# V2d_PCB.net
KiCad netlist of a schematic drawn in EAGLE
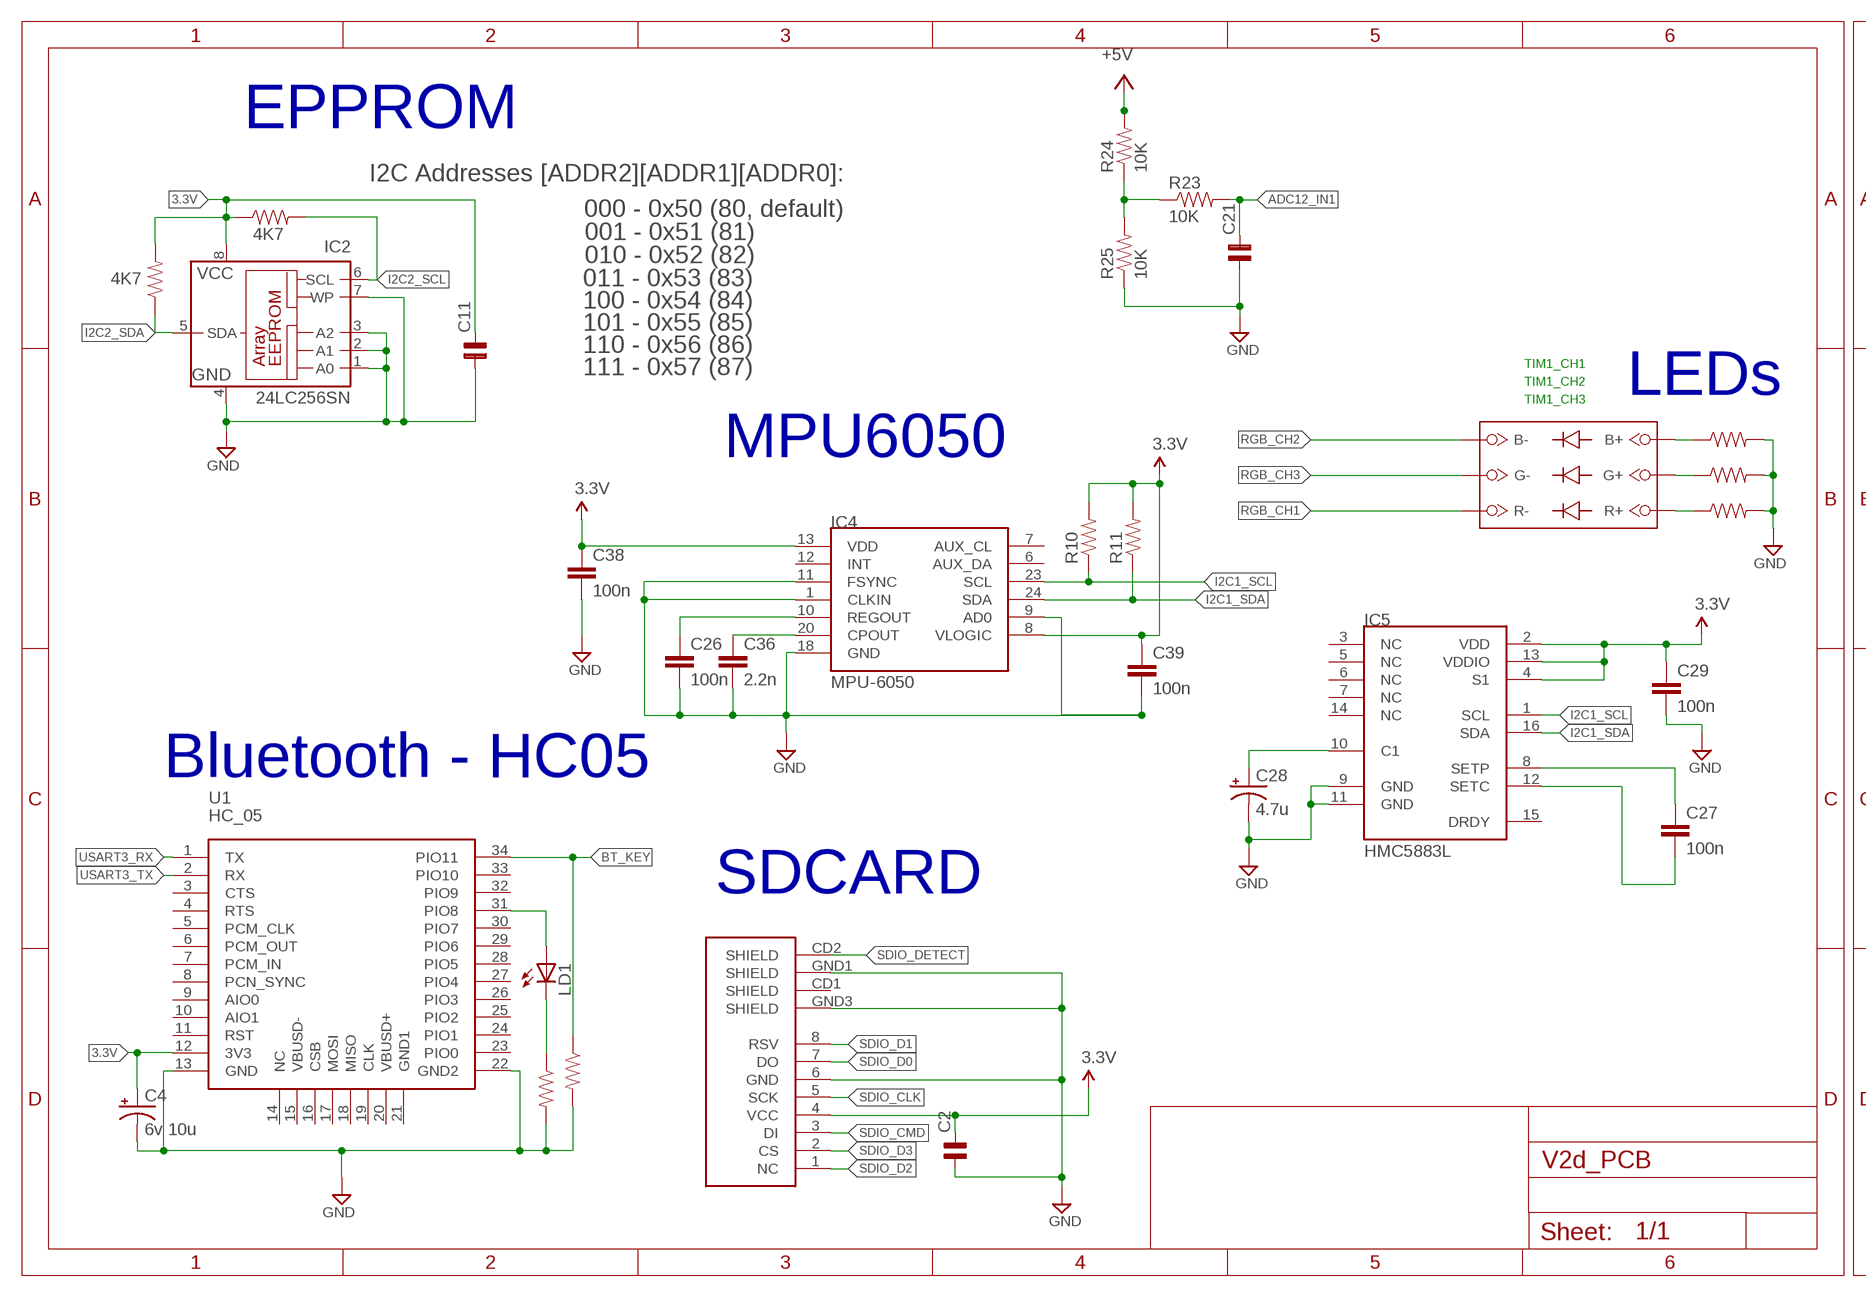
[diagram p0: schematic, sheet 1, part 1 of 2]
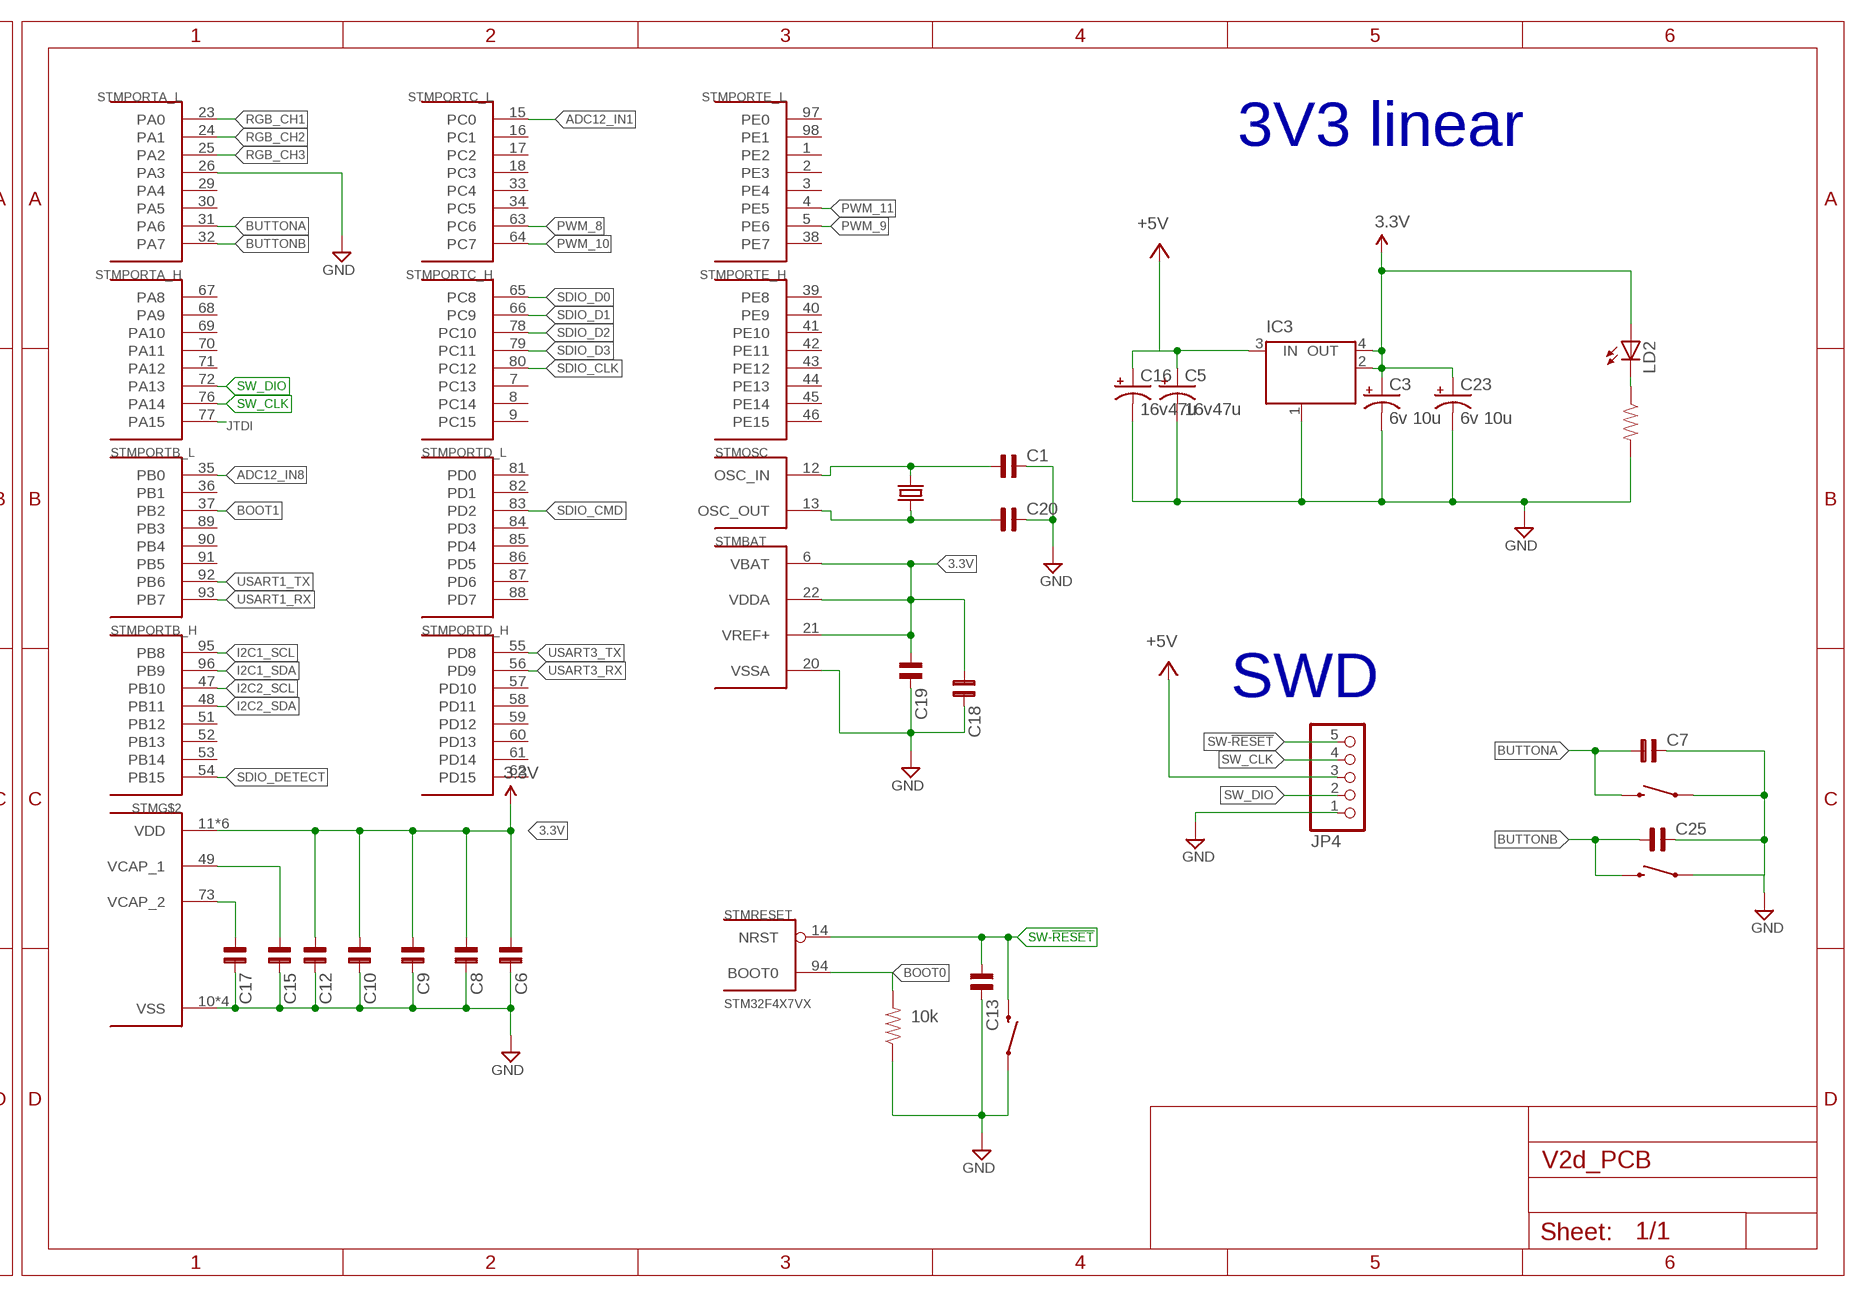
[diagram p1: schematic, sheet 1, part 2 of 2]

(export (version "E")
  (design (tool "Eeschema 10.0.6"))
  (components
    (comp (ref "C1")
      (value "C-NP-SMD-0603")
      (footprint "eagle-import:C-0603")
      (libsource (lib "eagle-import") (part "C-NP-SMD-0603"))
    )
    (comp (ref "C2")
      (value "C-NP-SMD-0603")
      (footprint "eagle-import:C-0603")
      (libsource (lib "eagle-import") (part "C-NP-SMD-0603"))
    )
    (comp (ref "C3")
      (value "6v 10u")
      (footprint "eagle-import:SMC_C")
      (libsource (lib "eagle-import") (part "CPOL-USSMCC"))
    )
    (comp (ref "C4")
      (value "6v 10u")
      (footprint "eagle-import:SMC_A")
      (libsource (lib "eagle-import") (part "CPOL-USSMCA"))
    )
    (comp (ref "C5")
      (value "16v47u")
      (footprint "eagle-import:SMC_C")
      (libsource (lib "eagle-import") (part "CPOL-USSMCC"))
    )
    (comp (ref "C6")
      (value "C-NP-SMD-0603")
      (footprint "eagle-import:C-0603")
      (libsource (lib "eagle-import") (part "C-NP-SMD-0603"))
    )
    (comp (ref "C7")
      (value "C-NP-SMD-0603")
      (footprint "eagle-import:C-0603")
      (libsource (lib "eagle-import") (part "C-NP-SMD-0603"))
    )
    (comp (ref "C8")
      (value "C-NP-SMD-0603")
      (footprint "eagle-import:C-0603")
      (libsource (lib "eagle-import") (part "C-NP-SMD-0603"))
    )
    (comp (ref "C9")
      (value "C-NP-SMD-0603")
      (footprint "eagle-import:C-0603")
      (libsource (lib "eagle-import") (part "C-NP-SMD-0603"))
    )
    (comp (ref "C10")
      (value "C-NP-SMD-0603")
      (footprint "eagle-import:C-0603")
      (libsource (lib "eagle-import") (part "C-NP-SMD-0603"))
    )
    (comp (ref "C11")
      (value "C-NP-SMD-0603")
      (footprint "eagle-import:C-0603")
      (libsource (lib "eagle-import") (part "C-NP-SMD-0603"))
    )
    (comp (ref "C12")
      (value "C-NP-SMD-0603")
      (footprint "eagle-import:C-0603")
      (libsource (lib "eagle-import") (part "C-NP-SMD-0603"))
    )
    (comp (ref "C13")
      (value "C-NP-SMD-0603")
      (footprint "eagle-import:C-0603")
      (libsource (lib "eagle-import") (part "C-NP-SMD-0603"))
    )
    (comp (ref "C15")
      (value "C-NP-SMD-0603")
      (footprint "eagle-import:C-0603")
      (libsource (lib "eagle-import") (part "C-NP-SMD-0603"))
    )
    (comp (ref "C16")
      (value "16v47u")
      (footprint "eagle-import:SMC_C")
      (libsource (lib "eagle-import") (part "CPOL-USSMCC"))
    )
    (comp (ref "C17")
      (value "C-NP-SMD-0603")
      (footprint "eagle-import:C-0603")
      (libsource (lib "eagle-import") (part "C-NP-SMD-0603"))
    )
    (comp (ref "C18")
      (value "C-NP-SMD-0603")
      (footprint "eagle-import:C-0603")
      (libsource (lib "eagle-import") (part "C-NP-SMD-0603"))
    )
    (comp (ref "C19")
      (value "C-NP-SMD-0603")
      (footprint "eagle-import:C-0603")
      (libsource (lib "eagle-import") (part "C-NP-SMD-0603"))
    )
    (comp (ref "C20")
      (value "C-NP-SMD-0603")
      (footprint "eagle-import:C-0603")
      (libsource (lib "eagle-import") (part "C-NP-SMD-0603"))
    )
    (comp (ref "C21")
      (value "C-NP-SMD-0603")
      (footprint "eagle-import:C-0603")
      (libsource (lib "eagle-import") (part "C-NP-SMD-0603"))
    )
    (comp (ref "C23")
      (value "6v 10u")
      (footprint "eagle-import:SMC_C")
      (libsource (lib "eagle-import") (part "CPOL-USSMCC"))
    )
    (comp (ref "C25")
      (value "C-NP-SMD-0603")
      (footprint "eagle-import:C-0603")
      (libsource (lib "eagle-import") (part "C-NP-SMD-0603"))
    )
    (comp (ref "C26")
      (value "100n")
      (footprint "eagle-import:SPARKFUN_0603-CAP")
      (libsource (lib "eagle-import") (part "SPARKFUN_CAP0603-CAP"))
    )
    (comp (ref "C27")
      (value "100n")
      (footprint "eagle-import:SPARKFUN_0603-CAP")
      (libsource (lib "eagle-import") (part "SPARKFUN_CAP0603-CAP"))
    )
    (comp (ref "C28")
      (value "4.7u")
      (footprint "eagle-import:SMC_A")
      (libsource (lib "eagle-import") (part "CPOL-USSMCA"))
    )
    (comp (ref "C29")
      (value "100n")
      (footprint "eagle-import:SPARKFUN_0603-CAP")
      (libsource (lib "eagle-import") (part "SPARKFUN_CAP0603-CAP"))
    )
    (comp (ref "C36")
      (value "2.2n")
      (footprint "eagle-import:SPARKFUN_0603-CAP")
      (libsource (lib "eagle-import") (part "SPARKFUN_CAP0603-CAP"))
    )
    (comp (ref "C38")
      (value "100n")
      (footprint "eagle-import:SPARKFUN_0603-CAP")
      (libsource (lib "eagle-import") (part "SPARKFUN_CAP0603-CAP"))
    )
    (comp (ref "C39")
      (value "100n")
      (footprint "eagle-import:SPARKFUN_0603-CAP")
      (libsource (lib "eagle-import") (part "SPARKFUN_CAP0603-CAP"))
    )
    (comp (ref "IC2")
      (value "24LC256SN")
      (footprint "eagle-import:SO-08")
      (fields (field (name "MF") "MICROCHIP") (field (name "MPN") "24LC256-I/SN"))
      (libsource (lib "eagle-import") (part "24SNLC256"))
    )
    (comp (ref "IC3")
      (value "LINEAR_MC33269ST-3.3T3")
      (footprint "eagle-import:LINEAR_SOT223")
      (libsource (lib "eagle-import") (part "LINEAR_MC33269ST-3.3T3"))
    )
    (comp (ref "IC4")
      (value "MPU-6050")
      (footprint "eagle-import:TESTING_QFN-24-4MM2")
      (libsource (lib "eagle-import") (part "TESTING_MPU-6050-1"))
    )
    (comp (ref "IC5")
      (value "HMC5883L")
      (footprint "eagle-import:SPARKFUN_16LPCC")
      (libsource (lib "eagle-import") (part "SPARKFUN_HMC5883LSMD"))
    )
    (comp (ref "JP4")
      (value "PINHD-1X5_2.54-90°")
      (footprint "eagle-import:1X05_90")
      (libsource (lib "eagle-import") (part "PINHD-1X5_2.54-90°"))
    )
    (comp (ref "LD1")
      (value "LEDCHIPLED_0603")
      (footprint "eagle-import:CHIPLED_0603")
      (libsource (lib "eagle-import") (part "LEDCHIPLED_0603"))
    )
    (comp (ref "LD2")
      (value "LEDCHIPLED_0603")
      (footprint "eagle-import:CHIPLED_0603")
      (libsource (lib "eagle-import") (part "LEDCHIPLED_0603"))
    )
    (comp (ref "R1")
      (value "10K")
      (footprint "eagle-import:SPARKFUN_0603-RES")
      (libsource (lib "eagle-import") (part "Robotech_RCL_SPARKFUN_RESISTOR0603-RES"))
    )
    (comp (ref "R2")
      (value "10K")
      (footprint "eagle-import:SPARKFUN_0603-RES")
      (libsource (lib "eagle-import") (part "Robotech_RCL_SPARKFUN_RESISTOR0603-RES"))
    )
    (comp (ref "R3")
      (value "10K")
      (footprint "eagle-import:SPARKFUN_0603-RES")
      (libsource (lib "eagle-import") (part "Robotech_RCL_SPARKFUN_RESISTOR0603-RES"))
    )
    (comp (ref "R5")
      (value "10K")
      (footprint "eagle-import:SPARKFUN_0603-RES")
      (libsource (lib "eagle-import") (part "Robotech_RCL_SPARKFUN_RESISTOR0603-RES"))
    )
    (comp (ref "R6")
      (value "10K")
      (footprint "eagle-import:SPARKFUN_0603-RES")
      (libsource (lib "eagle-import") (part "Robotech_RCL_SPARKFUN_RESISTOR0603-RES"))
    )
    (comp (ref "R7")
      (value "10k")
      (footprint "eagle-import:SPARKFUN_0603-RES")
      (libsource (lib "eagle-import") (part "Robotech_RCL_SPARKFUN_RESISTOR0603-RES"))
    )
    (comp (ref "R9")
      (value "10K")
      (footprint "eagle-import:SPARKFUN_0603-RES")
      (libsource (lib "eagle-import") (part "Robotech_RCL_SPARKFUN_RESISTOR0603-RES"))
    )
    (comp (ref "R10")
      (value "SPARKFUN_RESISTOR0603-RES")
      (footprint "eagle-import:SPARKFUN_0603-RES")
      (libsource (lib "eagle-import") (part "SPARKFUN_RESISTOR0603-RES"))
    )
    (comp (ref "R11")
      (value "SPARKFUN_RESISTOR0603-RES")
      (footprint "eagle-import:SPARKFUN_0603-RES")
      (libsource (lib "eagle-import") (part "SPARKFUN_RESISTOR0603-RES"))
    )
    (comp (ref "R15")
      (value "4K7")
      (footprint "eagle-import:SPARKFUN_0603-RES")
      (libsource (lib "eagle-import") (part "Robotech_RCL_SPARKFUN_RESISTOR0603-RES"))
    )
    (comp (ref "R16")
      (value "4K7")
      (footprint "eagle-import:SPARKFUN_0603-RES")
      (libsource (lib "eagle-import") (part "Robotech_RCL_SPARKFUN_RESISTOR0603-RES"))
    )
    (comp (ref "R23")
      (value "10K")
      (footprint "eagle-import:SPARKFUN_0603-RES")
      (libsource (lib "eagle-import") (part "Robotech_RCL_SPARKFUN_RESISTOR0603-RES"))
    )
    (comp (ref "R24")
      (value "10K")
      (footprint "eagle-import:SPARKFUN_0603-RES")
      (libsource (lib "eagle-import") (part "Robotech_RCL_SPARKFUN_RESISTOR0603-RES"))
    )
    (comp (ref "R25")
      (value "10K")
      (footprint "eagle-import:SPARKFUN_0603-RES")
      (libsource (lib "eagle-import") (part "Robotech_RCL_SPARKFUN_RESISTOR0603-RES"))
    )
    (comp (ref "S1")
      (value "RESET")
      (footprint "eagle-import:TACTILE-SWITCH-1101NE")
      (fields (field (name "PARTNO") "EVQ-P7J01P"))
      (libsource (lib "eagle-import") (part "SWITCH-MOMENTARY-2-SMD-1101NE"))
    )
    (comp (ref "S2")
      (value "RESET")
      (footprint "eagle-import:TACTILE-SWITCH-1101NE")
      (fields (field (name "PARTNO") "EVQ-P7J01P"))
      (libsource (lib "eagle-import") (part "SWITCH-MOMENTARY-2-SMD-1101NE"))
    )
    (comp (ref "S4")
      (value "RESET")
      (footprint "eagle-import:TACTILE-SWITCH-1101NE")
      (fields (field (name "PARTNO") "EVQ-P7J01P"))
      (libsource (lib "eagle-import") (part "SWITCH-MOMENTARY-2-SMD-1101NE"))
    )
    (comp (ref "SDCARD2")
      (value "microSD Socket")
      (footprint "eagle-import:MICRO-SD-SOCKET-PP")
      (libsource (lib "eagle-import") (part "USD-SOCKETNEW"))
    )
    (comp (ref "STM")
      (value "STM32F4X7VX")
      (footprint "eagle-import:TQFP100")
      (fields (field (name "PARTNO") "STM32F427VI"))
      (libsource (lib "eagle-import") (part "STM32F4X7VX"))
    )
    (comp (ref "U$12")
      (value "RGB_LED")
      (footprint "eagle-import:SMD")
      (libsource (lib "eagle-import") (part "RGB_LED"))
    )
    (comp (ref "U1")
      (value "HC_05")
      (footprint "eagle-import:BLUETOOTH_SMD")
      (libsource (lib "eagle-import") (part "HC_05"))
    )
    (comp (ref "Y1")
      (value "CRYSTALHC49US")
      (footprint "eagle-import:HC49US")
      (libsource (lib "eagle-import") (part "CRYSTALHC49US"))
    )
  )
  (nets
    (net (code "1") (name "+5V") (class "Default")
      (node (ref "C16") (pin "+") (pinfunction "+_+") (pintype "passive"))
      (node (ref "C5") (pin "+") (pinfunction "+_+") (pintype "passive"))
      (node (ref "IC3") (pin "3") (pinfunction "IN_3") (pintype "input"))
      (node (ref "JP4") (pin "3") (pinfunction "3_3") (pintype "passive"))
      (node (ref "R24") (pin "2") (pinfunction "2_2") (pintype "passive"))
    )
    (net (code "2") (name "/JTDI") (class "Default")
      (node (ref "STM") (pin "77") (pinfunction "PA15_77") (pintype "bidirectional"))
    )
    (net (code "3") (name "/SW-~{RESET}") (class "Default")
      (node (ref "C13") (pin "1") (pinfunction "1_1") (pintype "passive"))
      (node (ref "JP4") (pin "5") (pinfunction "5_5") (pintype "passive"))
      (node (ref "S1") (pin "P$2") (pinfunction "2_P$2") (pintype "passive"))
      (node (ref "STM") (pin "14") (pinfunction "NRST_14") (pintype "input"))
    )
    (net (code "4") (name "3.3V") (class "Default")
      (node (ref "C10") (pin "1") (pinfunction "1_1") (pintype "passive"))
      (node (ref "C11") (pin "2") (pinfunction "2_2") (pintype "passive"))
      (node (ref "C12") (pin "1") (pinfunction "1_1") (pintype "passive"))
      (node (ref "C18") (pin "1") (pinfunction "1_1") (pintype "passive"))
      (node (ref "C19") (pin "1") (pinfunction "1_1") (pintype "passive"))
      (node (ref "C2") (pin "2") (pinfunction "2_2") (pintype "passive"))
      (node (ref "C23") (pin "+") (pinfunction "+_+") (pintype "passive"))
      (node (ref "C29") (pin "1") (pinfunction "1_1") (pintype "passive"))
      (node (ref "C3") (pin "+") (pinfunction "+_+") (pintype "passive"))
      (node (ref "C38") (pin "1") (pinfunction "1_1") (pintype "passive"))
      (node (ref "C39") (pin "1") (pinfunction "1_1") (pintype "passive"))
      (node (ref "C4") (pin "+") (pinfunction "+_+") (pintype "passive"))
      (node (ref "C6") (pin "1") (pinfunction "1_1") (pintype "passive"))
      (node (ref "C8") (pin "1") (pinfunction "1_1") (pintype "passive"))
      (node (ref "C9") (pin "1") (pinfunction "1_1") (pintype "passive"))
      (node (ref "IC2") (pin "8") (pinfunction "VCC_8") (pintype "power_in"))
      (node (ref "IC3") (pin "2") (pinfunction "OUT_2") (pintype "passive"))
      (node (ref "IC3") (pin "4") (pinfunction "OUT_4") (pintype "passive"))
      (node (ref "IC4") (pin "13") (pinfunction "VDD_13") (pintype "bidirectional"))
      (node (ref "IC4") (pin "8") (pinfunction "VLOGIC_8") (pintype "bidirectional"))
      (node (ref "IC5") (pin "13") (pinfunction "VDDIO_13") (pintype "bidirectional"))
      (node (ref "IC5") (pin "2") (pinfunction "VDD_2") (pintype "bidirectional"))
      (node (ref "IC5") (pin "4") (pinfunction "S1_4") (pintype "bidirectional"))
      (node (ref "LD2") (pin "A") (pinfunction "A_A") (pintype "passive"))
      (node (ref "R10") (pin "2") (pinfunction "2_2") (pintype "passive"))
      (node (ref "R11") (pin "2") (pinfunction "2_2") (pintype "passive"))
      (node (ref "R15") (pin "1") (pinfunction "1_1") (pintype "passive"))
      (node (ref "R16") (pin "2") (pinfunction "2_2") (pintype "passive"))
      (node (ref "SDCARD2") (pin "4") (pinfunction "VCC_4") (pintype "bidirectional"))
      (node (ref "STM") (pin "100") (pinfunction "VDD_100") (pintype "power_in"))
      (node (ref "STM") (pin "11") (pinfunction "VDD_11") (pintype "power_in"))
      (node (ref "STM") (pin "19") (pinfunction "VDD_19") (pintype "power_in"))
      (node (ref "STM") (pin "21") (pinfunction "VREF+_21") (pintype "input"))
      (node (ref "STM") (pin "22") (pinfunction "VDDA_22") (pintype "power_in"))
      (node (ref "STM") (pin "28") (pinfunction "VDD_28") (pintype "power_in"))
      (node (ref "STM") (pin "50") (pinfunction "VDD_50") (pintype "power_in"))
      (node (ref "STM") (pin "6") (pinfunction "VBAT_6") (pintype "power_in"))
      (node (ref "STM") (pin "75") (pinfunction "VDD_75") (pintype "power_in"))
      (node (ref "U1") (pin "12") (pinfunction "3V3_12") (pintype "bidirectional"))
    )
    (net (code "5") (name "ADC12_IN1") (class "Default")
      (node (ref "C21") (pin "2") (pinfunction "2_2") (pintype "passive"))
      (node (ref "R23") (pin "2") (pinfunction "2_2") (pintype "passive"))
      (node (ref "STM") (pin "15") (pinfunction "PC0_15") (pintype "bidirectional"))
    )
    (net (code "6") (name "ADC12_IN8") (class "Default")
      (node (ref "STM") (pin "35") (pinfunction "PB0_35") (pintype "bidirectional"))
    )
    (net (code "7") (name "BOOT0") (class "Default")
      (node (ref "R7") (pin "2") (pinfunction "2_2") (pintype "passive"))
      (node (ref "STM") (pin "94") (pinfunction "BOOT0_94") (pintype "input"))
    )
    (net (code "8") (name "BOOT1") (class "Default")
      (node (ref "STM") (pin "37") (pinfunction "PB2_37") (pintype "bidirectional"))
    )
    (net (code "9") (name "BT_KEY") (class "Default")
      (node (ref "R5") (pin "1") (pinfunction "1_1") (pintype "passive"))
      (node (ref "U1") (pin "34") (pinfunction "PIO11_34") (pintype "bidirectional"))
    )
    (net (code "10") (name "BUTTONA") (class "Default")
      (node (ref "C7") (pin "1") (pinfunction "1_1") (pintype "passive"))
      (node (ref "S4") (pin "P$2") (pinfunction "2_P$2") (pintype "passive"))
      (node (ref "STM") (pin "31") (pinfunction "PA6_31") (pintype "bidirectional"))
    )
    (net (code "11") (name "BUTTONB") (class "Default")
      (node (ref "C25") (pin "1") (pinfunction "1_1") (pintype "passive"))
      (node (ref "S2") (pin "P$2") (pinfunction "2_P$2") (pintype "passive"))
      (node (ref "STM") (pin "32") (pinfunction "PA7_32") (pintype "bidirectional"))
    )
    (net (code "12") (name "GND") (class "Default")
      (node (ref "C1") (pin "2") (pinfunction "2_2") (pintype "passive"))
      (node (ref "C10") (pin "2") (pinfunction "2_2") (pintype "passive"))
      (node (ref "C11") (pin "1") (pinfunction "1_1") (pintype "passive"))
      (node (ref "C12") (pin "2") (pinfunction "2_2") (pintype "passive"))
      (node (ref "C13") (pin "2") (pinfunction "2_2") (pintype "passive"))
      (node (ref "C15") (pin "2") (pinfunction "2_2") (pintype "passive"))
      (node (ref "C16") (pin "-") (pinfunction "-_-") (pintype "passive"))
      (node (ref "C17") (pin "2") (pinfunction "2_2") (pintype "passive"))
      (node (ref "C18") (pin "2") (pinfunction "2_2") (pintype "passive"))
      (node (ref "C19") (pin "2") (pinfunction "2_2") (pintype "passive"))
      (node (ref "C2") (pin "1") (pinfunction "1_1") (pintype "passive"))
      (node (ref "C20") (pin "2") (pinfunction "2_2") (pintype "passive"))
      (node (ref "C21") (pin "1") (pinfunction "1_1") (pintype "passive"))
      (node (ref "C23") (pin "-") (pinfunction "-_-") (pintype "passive"))
      (node (ref "C25") (pin "2") (pinfunction "2_2") (pintype "passive"))
      (node (ref "C26") (pin "2") (pinfunction "2_2") (pintype "passive"))
      (node (ref "C28") (pin "-") (pinfunction "-_-") (pintype "passive"))
      (node (ref "C29") (pin "2") (pinfunction "2_2") (pintype "passive"))
      (node (ref "C3") (pin "-") (pinfunction "-_-") (pintype "passive"))
      (node (ref "C36") (pin "2") (pinfunction "2_2") (pintype "passive"))
      (node (ref "C38") (pin "2") (pinfunction "2_2") (pintype "passive"))
      (node (ref "C39") (pin "2") (pinfunction "2_2") (pintype "passive"))
      (node (ref "C4") (pin "-") (pinfunction "-_-") (pintype "passive"))
      (node (ref "C5") (pin "-") (pinfunction "-_-") (pintype "passive"))
      (node (ref "C6") (pin "2") (pinfunction "2_2") (pintype "passive"))
      (node (ref "C7") (pin "2") (pinfunction "2_2") (pintype "passive"))
      (node (ref "C8") (pin "2") (pinfunction "2_2") (pintype "passive"))
      (node (ref "C9") (pin "2") (pinfunction "2_2") (pintype "passive"))
      (node (ref "IC2") (pin "1") (pinfunction "A0_1") (pintype "input"))
      (node (ref "IC2") (pin "2") (pinfunction "A1_2") (pintype "input"))
      (node (ref "IC2") (pin "3") (pinfunction "A2_3") (pintype "input"))
      (node (ref "IC2") (pin "4") (pinfunction "GND_4") (pintype "power_in"))
      (node (ref "IC2") (pin "7") (pinfunction "WP_7") (pintype "input"))
      (node (ref "IC3") (pin "1") (pinfunction "GND/ADJ_1") (pintype "input"))
      (node (ref "IC4") (pin "1") (pinfunction "CLKIN_1") (pintype "bidirectional"))
      (node (ref "IC4") (pin "11") (pinfunction "FSYNC_11") (pintype "bidirectional"))
      (node (ref "IC4") (pin "18") (pinfunction "GND_18") (pintype "bidirectional"))
      (node (ref "IC4") (pin "9") (pinfunction "AD0_9") (pintype "bidirectional"))
      (node (ref "IC5") (pin "11") (pinfunction "GND_11") (pintype "bidirectional"))
      (node (ref "IC5") (pin "9") (pinfunction "GND_9") (pintype "bidirectional"))
      (node (ref "JP4") (pin "1") (pinfunction "1_1") (pintype "passive"))
      (node (ref "R1") (pin "2") (pinfunction "2_2") (pintype "passive"))
      (node (ref "R2") (pin "2") (pinfunction "2_2") (pintype "passive"))
      (node (ref "R25") (pin "1") (pinfunction "1_1") (pintype "passive"))
      (node (ref "R3") (pin "2") (pinfunction "2_2") (pintype "passive"))
      (node (ref "R5") (pin "2") (pinfunction "2_2") (pintype "passive"))
      (node (ref "R6") (pin "2") (pinfunction "2_2") (pintype "passive"))
      (node (ref "R7") (pin "1") (pinfunction "1_1") (pintype "passive"))
      (node (ref "R9") (pin "2") (pinfunction "2_2") (pintype "passive"))
      (node (ref "S1") (pin "P$1") (pinfunction "1_P$1") (pintype "passive"))
      (node (ref "S2") (pin "P$1") (pinfunction "1_P$1") (pintype "passive"))
      (node (ref "S4") (pin "P$1") (pinfunction "1_P$1") (pintype "passive"))
      (node (ref "SDCARD2") (pin "6") (pinfunction "GND_6") (pintype "bidirectional"))
      (node (ref "SDCARD2") (pin "GND1") (pinfunction "SHIELD_GND1") (pintype "bidirectional"))
      (node (ref "SDCARD2") (pin "GND3") (pinfunction "SHIELD_GND3") (pintype "bidirectional"))
      (node (ref "STM") (pin "10") (pinfunction "VSS_10") (pintype "power_in"))
      (node (ref "STM") (pin "20") (pinfunction "VSSA_20") (pintype "power_in"))
      (node (ref "STM") (pin "26") (pinfunction "PA3_26") (pintype "bidirectional"))
      (node (ref "STM") (pin "27") (pinfunction "VSS_27") (pintype "power_in"))
      (node (ref "STM") (pin "74") (pinfunction "VSS_74") (pintype "power_in"))
      (node (ref "STM") (pin "99") (pinfunction "VSS_99") (pintype "power_in"))
      (node (ref "U1") (pin "13") (pinfunction "GND_13") (pintype "bidirectional"))
      (node (ref "U1") (pin "22") (pinfunction "GND2_22") (pintype "bidirectional"))
    )
    (net (code "13") (name "I2C1_SCL") (class "Default")
      (node (ref "IC4") (pin "23") (pinfunction "SCL_23") (pintype "bidirectional"))
      (node (ref "IC5") (pin "1") (pinfunction "SCL_1") (pintype "bidirectional"))
      (node (ref "R10") (pin "1") (pinfunction "1_1") (pintype "passive"))
      (node (ref "STM") (pin "95") (pinfunction "PB8_95") (pintype "bidirectional"))
    )
    (net (code "14") (name "I2C1_SDA") (class "Default")
      (node (ref "IC4") (pin "24") (pinfunction "SDA_24") (pintype "bidirectional"))
      (node (ref "IC5") (pin "16") (pinfunction "SDA_16") (pintype "bidirectional"))
      (node (ref "R11") (pin "1") (pinfunction "1_1") (pintype "passive"))
      (node (ref "STM") (pin "96") (pinfunction "PB9_96") (pintype "bidirectional"))
    )
    (net (code "15") (name "I2C2_SCL") (class "Default")
      (node (ref "IC2") (pin "6") (pinfunction "SCL_6") (pintype "input"))
      (node (ref "R15") (pin "2") (pinfunction "2_2") (pintype "passive"))
      (node (ref "STM") (pin "47") (pinfunction "PB10_47") (pintype "bidirectional"))
    )
    (net (code "16") (name "I2C2_SDA") (class "Default")
      (node (ref "IC2") (pin "5") (pinfunction "SDA_5") (pintype "bidirectional"))
      (node (ref "R16") (pin "1") (pinfunction "1_1") (pintype "passive"))
      (node (ref "STM") (pin "48") (pinfunction "PB11_48") (pintype "bidirectional"))
    )
    (net (code "17") (name "Net-(IC4-CPOUT)") (class "Default")
      (node (ref "C36") (pin "1") (pinfunction "1_1") (pintype "passive"))
      (node (ref "IC4") (pin "20") (pinfunction "CPOUT_20") (pintype "bidirectional"))
    )
    (net (code "18") (name "Net-(IC4-REGOUT)") (class "Default")
      (node (ref "C26") (pin "1") (pinfunction "1_1") (pintype "passive"))
      (node (ref "IC4") (pin "10") (pinfunction "REGOUT_10") (pintype "bidirectional"))
    )
    (net (code "19") (name "Net-(IC5-C1)") (class "Default")
      (node (ref "C28") (pin "+") (pinfunction "+_+") (pintype "passive"))
      (node (ref "IC5") (pin "10") (pinfunction "C1_10") (pintype "bidirectional"))
    )
    (net (code "20") (name "Net-(IC5-SETC)") (class "Default")
      (node (ref "C27") (pin "2") (pinfunction "2_2") (pintype "passive"))
      (node (ref "IC5") (pin "12") (pinfunction "SETC_12") (pintype "bidirectional"))
    )
    (net (code "21") (name "Net-(IC5-SETP)") (class "Default")
      (node (ref "C27") (pin "1") (pinfunction "1_1") (pintype "passive"))
      (node (ref "IC5") (pin "8") (pinfunction "SETP_8") (pintype "bidirectional"))
    )
    (net (code "22") (name "Net-(LD1-PadC)") (class "Default")
      (node (ref "LD1") (pin "C") (pinfunction "C_C") (pintype "passive"))
      (node (ref "R9") (pin "1") (pinfunction "1_1") (pintype "passive"))
    )
    (net (code "23") (name "Net-(LD2-PadC)") (class "Default")
      (node (ref "LD2") (pin "C") (pinfunction "C_C") (pintype "passive"))
      (node (ref "R1") (pin "1") (pinfunction "1_1") (pintype "passive"))
    )
    (net (code "24") (name "Net-(R2-Pad1)") (class "Default")
      (node (ref "R2") (pin "1") (pinfunction "1_1") (pintype "passive"))
      (node (ref "U$12") (pin "B+") (pinfunction "B+_B+") (pintype "bidirectional"))
    )
    (net (code "25") (name "Net-(R3-Pad1)") (class "Default")
      (node (ref "R3") (pin "1") (pinfunction "1_1") (pintype "passive"))
      (node (ref "U$12") (pin "G+") (pinfunction "G+_G+") (pintype "bidirectional"))
    )
    (net (code "26") (name "Net-(R6-Pad1)") (class "Default")
      (node (ref "R6") (pin "1") (pinfunction "1_1") (pintype "passive"))
      (node (ref "U$12") (pin "R+") (pinfunction "R+_R+") (pintype "bidirectional"))
    )
    (net (code "27") (name "Net-(R23-Pad1)") (class "Default")
      (node (ref "R23") (pin "1") (pinfunction "1_1") (pintype "passive"))
      (node (ref "R24") (pin "1") (pinfunction "1_1") (pintype "passive"))
      (node (ref "R25") (pin "2") (pinfunction "2_2") (pintype "passive"))
    )
    (net (code "28") (name "Net-(STMB-VCAP_1)") (class "Default")
      (node (ref "C15") (pin "1") (pinfunction "1_1") (pintype "passive"))
      (node (ref "STM") (pin "49") (pinfunction "VCAP_1_49") (pintype "power_in"))
    )
    (net (code "29") (name "Net-(STMB-VCAP_2)") (class "Default")
      (node (ref "C17") (pin "1") (pinfunction "1_1") (pintype "passive"))
      (node (ref "STM") (pin "73") (pinfunction "VCAP_2_73") (pintype "power_in"))
    )
    (net (code "30") (name "Net-(STMC-OSC_IN)") (class "Default")
      (node (ref "C1") (pin "1") (pinfunction "1_1") (pintype "passive"))
      (node (ref "STM") (pin "12") (pinfunction "OSC_IN_12") (pintype "input"))
      (node (ref "Y1") (pin "2") (pinfunction "2_2") (pintype "passive"))
    )
    (net (code "31") (name "Net-(STMC-OSC_OUT)") (class "Default")
      (node (ref "C20") (pin "1") (pinfunction "1_1") (pintype "passive"))
      (node (ref "STM") (pin "13") (pinfunction "OSC_OUT_13") (pintype "output"))
      (node (ref "Y1") (pin "1") (pinfunction "1_1") (pintype "passive"))
    )
    (net (code "32") (name "Net-(U1-PIO8)") (class "Default")
      (node (ref "LD1") (pin "A") (pinfunction "A_A") (pintype "passive"))
      (node (ref "U1") (pin "31") (pinfunction "PIO8_31") (pintype "bidirectional"))
    )
    (net (code "33") (name "PWM_8") (class "Default")
      (node (ref "STM") (pin "63") (pinfunction "PC6_63") (pintype "bidirectional"))
    )
    (net (code "34") (name "PWM_9") (class "Default")
      (node (ref "STM") (pin "5") (pinfunction "PE6_5") (pintype "bidirectional"))
    )
    (net (code "35") (name "PWM_10") (class "Default")
      (node (ref "STM") (pin "64") (pinfunction "PC7_64") (pintype "bidirectional"))
    )
    (net (code "36") (name "PWM_11") (class "Default")
      (node (ref "STM") (pin "4") (pinfunction "PE5_4") (pintype "bidirectional"))
    )
    (net (code "37") (name "RGB_CH1") (class "Default")
      (node (ref "STM") (pin "23") (pinfunction "PA0_23") (pintype "bidirectional"))
      (node (ref "U$12") (pin "R-") (pinfunction "R-_R-") (pintype "bidirectional"))
    )
    (net (code "38") (name "RGB_CH2") (class "Default")
      (node (ref "STM") (pin "24") (pinfunction "PA1_24") (pintype "bidirectional"))
      (node (ref "U$12") (pin "B-") (pinfunction "B-_B-") (pintype "bidirectional"))
    )
    (net (code "39") (name "RGB_CH3") (class "Default")
      (node (ref "STM") (pin "25") (pinfunction "PA2_25") (pintype "bidirectional"))
      (node (ref "U$12") (pin "G-") (pinfunction "G-_G-") (pintype "bidirectional"))
    )
    (net (code "40") (name "SDIO_CLK") (class "Default")
      (node (ref "SDCARD2") (pin "5") (pinfunction "SCK_5") (pintype "bidirectional"))
      (node (ref "STM") (pin "80") (pinfunction "PC12_80") (pintype "bidirectional"))
    )
    (net (code "41") (name "SDIO_CMD") (class "Default")
      (node (ref "SDCARD2") (pin "3") (pinfunction "DI_3") (pintype "bidirectional"))
      (node (ref "STM") (pin "83") (pinfunction "PD2_83") (pintype "bidirectional"))
    )
    (net (code "42") (name "SDIO_D0") (class "Default")
      (node (ref "SDCARD2") (pin "7") (pinfunction "DO_7") (pintype "bidirectional"))
      (node (ref "STM") (pin "65") (pinfunction "PC8_65") (pintype "bidirectional"))
    )
    (net (code "43") (name "SDIO_D1") (class "Default")
      (node (ref "SDCARD2") (pin "8") (pinfunction "RSV_8") (pintype "bidirectional"))
      (node (ref "STM") (pin "66") (pinfunction "PC9_66") (pintype "bidirectional"))
    )
    (net (code "44") (name "SDIO_D2") (class "Default")
      (node (ref "SDCARD2") (pin "1") (pinfunction "NC_1") (pintype "bidirectional"))
      (node (ref "STM") (pin "78") (pinfunction "PC10_78") (pintype "bidirectional"))
    )
    (net (code "45") (name "SDIO_D3") (class "Default")
      (node (ref "SDCARD2") (pin "2") (pinfunction "CS_2") (pintype "bidirectional"))
      (node (ref "STM") (pin "79") (pinfunction "PC11_79") (pintype "bidirectional"))
    )
    (net (code "46") (name "SDIO_DETECT") (class "Default")
      (node (ref "SDCARD2") (pin "CD2") (pinfunction "SHIELD_CD2") (pintype "bidirectional"))
      (node (ref "STM") (pin "54") (pinfunction "PB15_54") (pintype "bidirectional"))
    )
    (net (code "47") (name "SW_CLK") (class "Default")
      (node (ref "JP4") (pin "4") (pinfunction "4_4") (pintype "passive"))
      (node (ref "STM") (pin "76") (pinfunction "PA14_76") (pintype "bidirectional"))
    )
    (net (code "48") (name "SW_DIO") (class "Default")
      (node (ref "JP4") (pin "2") (pinfunction "2_2") (pintype "passive"))
      (node (ref "STM") (pin "72") (pinfunction "PA13_72") (pintype "bidirectional"))
    )
    (net (code "49") (name "USART1_RX") (class "Default")
      (node (ref "STM") (pin "93") (pinfunction "PB7_93") (pintype "bidirectional"))
    )
    (net (code "50") (name "USART1_TX") (class "Default")
      (node (ref "STM") (pin "92") (pinfunction "PB6_92") (pintype "bidirectional"))
    )
    (net (code "51") (name "USART3_RX") (class "Default")
      (node (ref "STM") (pin "56") (pinfunction "PD9_56") (pintype "bidirectional"))
      (node (ref "U1") (pin "1") (pinfunction "TX_1") (pintype "bidirectional"))
    )
    (net (code "52") (name "USART3_TX") (class "Default")
      (node (ref "STM") (pin "55") (pinfunction "PD8_55") (pintype "bidirectional"))
      (node (ref "U1") (pin "2") (pinfunction "RX_2") (pintype "bidirectional"))
    )
    (net (code "53") (name "unconnected-(IC4-AUX_CL-Pad7)") (class "Default")
      (node (ref "IC4") (pin "7") (pinfunction "AUX_CL_7") (pintype "bidirectional"))
    )
    (net (code "54") (name "unconnected-(IC4-AUX_DA-Pad6)") (class "Default")
      (node (ref "IC4") (pin "6") (pinfunction "AUX_DA_6") (pintype "bidirectional"))
    )
    (net (code "55") (name "unconnected-(IC4-INT-Pad12)") (class "Default")
      (node (ref "IC4") (pin "12") (pinfunction "INT_12") (pintype "bidirectional"))
    )
    (net (code "56") (name "unconnected-(IC5-DRDY-Pad15)") (class "Default")
      (node (ref "IC5") (pin "15") (pinfunction "DRDY_15") (pintype "bidirectional"))
    )
    (net (code "57") (name "unconnected-(IC5-NC-Pad3)") (class "Default")
      (node (ref "IC5") (pin "3") (pinfunction "NC_3") (pintype "bidirectional"))
    )
    (net (code "58") (name "unconnected-(IC5-NC-Pad5)") (class "Default")
      (node (ref "IC5") (pin "5") (pinfunction "NC_5") (pintype "bidirectional"))
    )
    (net (code "59") (name "unconnected-(IC5-NC-Pad6)") (class "Default")
      (node (ref "IC5") (pin "6") (pinfunction "NC_6") (pintype "bidirectional"))
    )
    (net (code "60") (name "unconnected-(IC5-NC-Pad7)") (class "Default")
      (node (ref "IC5") (pin "7") (pinfunction "NC_7") (pintype "bidirectional"))
    )
    (net (code "61") (name "unconnected-(IC5-NC-Pad14)") (class "Default")
      (node (ref "IC5") (pin "14") (pinfunction "NC_14") (pintype "bidirectional"))
    )
    (net (code "62") (name "unconnected-(SDCARD2-SHIELD-PadCD1)") (class "Default")
      (node (ref "SDCARD2") (pin "CD1") (pinfunction "SHIELD_CD1") (pintype "bidirectional"))
    )
    (net (code "63") (name "unconnected-(STMD-PA8-Pad67)") (class "Default")
      (node (ref "STM") (pin "67") (pinfunction "PA8_67") (pintype "bidirectional"))
    )
    (net (code "64") (name "unconnected-(STMD-PA9-Pad68)") (class "Default")
      (node (ref "STM") (pin "68") (pinfunction "PA9_68") (pintype "bidirectional"))
    )
    (net (code "65") (name "unconnected-(STMD-PA10-Pad69)") (class "Default")
      (node (ref "STM") (pin "69") (pinfunction "PA10_69") (pintype "bidirectional"))
    )
    (net (code "66") (name "unconnected-(STMD-PA11-Pad70)") (class "Default")
      (node (ref "STM") (pin "70") (pinfunction "PA11_70") (pintype "bidirectional"))
    )
    (net (code "67") (name "unconnected-(STMD-PA12-Pad71)") (class "Default")
      (node (ref "STM") (pin "71") (pinfunction "PA12_71") (pintype "bidirectional"))
    )
    (net (code "68") (name "unconnected-(STME-PA4-Pad29)") (class "Default")
      (node (ref "STM") (pin "29") (pinfunction "PA4_29") (pintype "bidirectional"))
    )
    (net (code "69") (name "unconnected-(STME-PA5-Pad30)") (class "Default")
      (node (ref "STM") (pin "30") (pinfunction "PA5_30") (pintype "bidirectional"))
    )
    (net (code "70") (name "unconnected-(STMF-PB12-Pad51)") (class "Default")
      (node (ref "STM") (pin "51") (pinfunction "PB12_51") (pintype "bidirectional"))
    )
    (net (code "71") (name "unconnected-(STMF-PB13-Pad52)") (class "Default")
      (node (ref "STM") (pin "52") (pinfunction "PB13_52") (pintype "bidirectional"))
    )
    (net (code "72") (name "unconnected-(STMF-PB14-Pad53)") (class "Default")
      (node (ref "STM") (pin "53") (pinfunction "PB14_53") (pintype "bidirectional"))
    )
    (net (code "73") (name "unconnected-(STMG-PB1-Pad36)") (class "Default")
      (node (ref "STM") (pin "36") (pinfunction "PB1_36") (pintype "bidirectional"))
    )
    (net (code "74") (name "unconnected-(STMG-PB3-Pad89)") (class "Default")
      (node (ref "STM") (pin "89") (pinfunction "PB3_89") (pintype "bidirectional"))
    )
    (net (code "75") (name "unconnected-(STMG-PB4-Pad90)") (class "Default")
      (node (ref "STM") (pin "90") (pinfunction "PB4_90") (pintype "bidirectional"))
    )
    (net (code "76") (name "unconnected-(STMG-PB5-Pad91)") (class "Default")
      (node (ref "STM") (pin "91") (pinfunction "PB5_91") (pintype "bidirectional"))
    )
    (net (code "77") (name "unconnected-(STMH-PC13-Pad7)") (class "Default")
      (node (ref "STM") (pin "7") (pinfunction "PC13_7") (pintype "bidirectional"))
    )
    (net (code "78") (name "unconnected-(STMH-PC14-Pad8)") (class "Default")
      (node (ref "STM") (pin "8") (pinfunction "PC14_8") (pintype "bidirectional"))
    )
    (net (code "79") (name "unconnected-(STMH-PC15-Pad9)") (class "Default")
      (node (ref "STM") (pin "9") (pinfunction "PC15_9") (pintype "bidirectional"))
    )
    (net (code "80") (name "unconnected-(STMI-PC1-Pad16)") (class "Default")
      (node (ref "STM") (pin "16") (pinfunction "PC1_16") (pintype "bidirectional"))
    )
    (net (code "81") (name "unconnected-(STMI-PC2-Pad17)") (class "Default")
      (node (ref "STM") (pin "17") (pinfunction "PC2_17") (pintype "bidirectional"))
    )
    (net (code "82") (name "unconnected-(STMI-PC3-Pad18)") (class "Default")
      (node (ref "STM") (pin "18") (pinfunction "PC3_18") (pintype "bidirectional"))
    )
    (net (code "83") (name "unconnected-(STMI-PC4-Pad33)") (class "Default")
      (node (ref "STM") (pin "33") (pinfunction "PC4_33") (pintype "bidirectional"))
    )
    (net (code "84") (name "unconnected-(STMI-PC5-Pad34)") (class "Default")
      (node (ref "STM") (pin "34") (pinfunction "PC5_34") (pintype "bidirectional"))
    )
    (net (code "85") (name "unconnected-(STMJ-PD10-Pad57)") (class "Default")
      (node (ref "STM") (pin "57") (pinfunction "PD10_57") (pintype "bidirectional"))
    )
    (net (code "86") (name "unconnected-(STMJ-PD11-Pad58)") (class "Default")
      (node (ref "STM") (pin "58") (pinfunction "PD11_58") (pintype "bidirectional"))
    )
    (net (code "87") (name "unconnected-(STMJ-PD12-Pad59)") (class "Default")
      (node (ref "STM") (pin "59") (pinfunction "PD12_59") (pintype "bidirectional"))
    )
    (net (code "88") (name "unconnected-(STMJ-PD13-Pad60)") (class "Default")
      (node (ref "STM") (pin "60") (pinfunction "PD13_60") (pintype "bidirectional"))
    )
    (net (code "89") (name "unconnected-(STMJ-PD14-Pad61)") (class "Default")
      (node (ref "STM") (pin "61") (pinfunction "PD14_61") (pintype "bidirectional"))
    )
    (net (code "90") (name "unconnected-(STMJ-PD15-Pad62)") (class "Default")
      (node (ref "STM") (pin "62") (pinfunction "PD15_62") (pintype "bidirectional"))
    )
    (net (code "91") (name "unconnected-(STMK-PD0-Pad81)") (class "Default")
      (node (ref "STM") (pin "81") (pinfunction "PD0_81") (pintype "bidirectional"))
    )
    (net (code "92") (name "unconnected-(STMK-PD1-Pad82)") (class "Default")
      (node (ref "STM") (pin "82") (pinfunction "PD1_82") (pintype "bidirectional"))
    )
    (net (code "93") (name "unconnected-(STMK-PD3-Pad84)") (class "Default")
      (node (ref "STM") (pin "84") (pinfunction "PD3_84") (pintype "bidirectional"))
    )
    (net (code "94") (name "unconnected-(STMK-PD4-Pad85)") (class "Default")
      (node (ref "STM") (pin "85") (pinfunction "PD4_85") (pintype "bidirectional"))
    )
    (net (code "95") (name "unconnected-(STMK-PD5-Pad86)") (class "Default")
      (node (ref "STM") (pin "86") (pinfunction "PD5_86") (pintype "bidirectional"))
    )
    (net (code "96") (name "unconnected-(STMK-PD6-Pad87)") (class "Default")
      (node (ref "STM") (pin "87") (pinfunction "PD6_87") (pintype "bidirectional"))
    )
    (net (code "97") (name "unconnected-(STMK-PD7-Pad88)") (class "Default")
      (node (ref "STM") (pin "88") (pinfunction "PD7_88") (pintype "bidirectional"))
    )
    (net (code "98") (name "unconnected-(STML-PE8-Pad39)") (class "Default")
      (node (ref "STM") (pin "39") (pinfunction "PE8_39") (pintype "bidirectional"))
    )
    (net (code "99") (name "unconnected-(STML-PE9-Pad40)") (class "Default")
      (node (ref "STM") (pin "40") (pinfunction "PE9_40") (pintype "bidirectional"))
    )
    (net (code "100") (name "unconnected-(STML-PE10-Pad41)") (class "Default")
      (node (ref "STM") (pin "41") (pinfunction "PE10_41") (pintype "bidirectional"))
    )
    (net (code "101") (name "unconnected-(STML-PE11-Pad42)") (class "Default")
      (node (ref "STM") (pin "42") (pinfunction "PE11_42") (pintype "bidirectional"))
    )
    (net (code "102") (name "unconnected-(STML-PE12-Pad43)") (class "Default")
      (node (ref "STM") (pin "43") (pinfunction "PE12_43") (pintype "bidirectional"))
    )
    (net (code "103") (name "unconnected-(STML-PE13-Pad44)") (class "Default")
      (node (ref "STM") (pin "44") (pinfunction "PE13_44") (pintype "bidirectional"))
    )
    (net (code "104") (name "unconnected-(STML-PE14-Pad45)") (class "Default")
      (node (ref "STM") (pin "45") (pinfunction "PE14_45") (pintype "bidirectional"))
    )
    (net (code "105") (name "unconnected-(STML-PE15-Pad46)") (class "Default")
      (node (ref "STM") (pin "46") (pinfunction "PE15_46") (pintype "bidirectional"))
    )
    (net (code "106") (name "unconnected-(STMM-PE0-Pad97)") (class "Default")
      (node (ref "STM") (pin "97") (pinfunction "PE0_97") (pintype "bidirectional"))
    )
    (net (code "107") (name "unconnected-(STMM-PE1-Pad98)") (class "Default")
      (node (ref "STM") (pin "98") (pinfunction "PE1_98") (pintype "bidirectional"))
    )
    (net (code "108") (name "unconnected-(STMM-PE2-Pad1)") (class "Default")
      (node (ref "STM") (pin "1") (pinfunction "PE2_1") (pintype "bidirectional"))
    )
    (net (code "109") (name "unconnected-(STMM-PE3-Pad2)") (class "Default")
      (node (ref "STM") (pin "2") (pinfunction "PE3_2") (pintype "bidirectional"))
    )
    (net (code "110") (name "unconnected-(STMM-PE4-Pad3)") (class "Default")
      (node (ref "STM") (pin "3") (pinfunction "PE4_3") (pintype "bidirectional"))
    )
    (net (code "111") (name "unconnected-(STMM-PE7-Pad38)") (class "Default")
      (node (ref "STM") (pin "38") (pinfunction "PE7_38") (pintype "bidirectional"))
    )
    (net (code "112") (name "unconnected-(U1-AIO0-Pad9)") (class "Default")
      (node (ref "U1") (pin "9") (pinfunction "AIO0_9") (pintype "bidirectional"))
    )
    (net (code "113") (name "unconnected-(U1-AIO1-Pad10)") (class "Default")
      (node (ref "U1") (pin "10") (pinfunction "AIO1_10") (pintype "bidirectional"))
    )
    (net (code "114") (name "unconnected-(U1-CLK-Pad19)") (class "Default")
      (node (ref "U1") (pin "19") (pinfunction "CLK_19") (pintype "bidirectional"))
    )
    (net (code "115") (name "unconnected-(U1-CSB-Pad16)") (class "Default")
      (node (ref "U1") (pin "16") (pinfunction "CSB_16") (pintype "bidirectional"))
    )
    (net (code "116") (name "unconnected-(U1-CTS-Pad3)") (class "Default")
      (node (ref "U1") (pin "3") (pinfunction "CTS_3") (pintype "bidirectional"))
    )
    (net (code "117") (name "unconnected-(U1-GND1-Pad21)") (class "Default")
      (node (ref "U1") (pin "21") (pinfunction "GND1_21") (pintype "bidirectional"))
    )
    (net (code "118") (name "unconnected-(U1-MISO-Pad18)") (class "Default")
      (node (ref "U1") (pin "18") (pinfunction "MISO_18") (pintype "bidirectional"))
    )
    (net (code "119") (name "unconnected-(U1-MOSI-Pad17)") (class "Default")
      (node (ref "U1") (pin "17") (pinfunction "MOSI_17") (pintype "bidirectional"))
    )
    (net (code "120") (name "unconnected-(U1-NC-Pad14)") (class "Default")
      (node (ref "U1") (pin "14") (pinfunction "NC_14") (pintype "bidirectional"))
    )
    (net (code "121") (name "unconnected-(U1-PCM_CLK-Pad5)") (class "Default")
      (node (ref "U1") (pin "5") (pinfunction "PCM_CLK_5") (pintype "bidirectional"))
    )
    (net (code "122") (name "unconnected-(U1-PCM_IN-Pad7)") (class "Default")
      (node (ref "U1") (pin "7") (pinfunction "PCM_IN_7") (pintype "bidirectional"))
    )
    (net (code "123") (name "unconnected-(U1-PCM_OUT-Pad6)") (class "Default")
      (node (ref "U1") (pin "6") (pinfunction "PCM_OUT_6") (pintype "bidirectional"))
    )
    (net (code "124") (name "unconnected-(U1-PCN_SYNC-Pad8)") (class "Default")
      (node (ref "U1") (pin "8") (pinfunction "PCN_SYNC_8") (pintype "bidirectional"))
    )
    (net (code "125") (name "unconnected-(U1-PIO0-Pad23)") (class "Default")
      (node (ref "U1") (pin "23") (pinfunction "PIO0_23") (pintype "bidirectional"))
    )
    (net (code "126") (name "unconnected-(U1-PIO1-Pad24)") (class "Default")
      (node (ref "U1") (pin "24") (pinfunction "PIO1_24") (pintype "bidirectional"))
    )
    (net (code "127") (name "unconnected-(U1-PIO2-Pad25)") (class "Default")
      (node (ref "U1") (pin "25") (pinfunction "PIO2_25") (pintype "bidirectional"))
    )
    (net (code "128") (name "unconnected-(U1-PIO3-Pad26)") (class "Default")
      (node (ref "U1") (pin "26") (pinfunction "PIO3_26") (pintype "bidirectional"))
    )
    (net (code "129") (name "unconnected-(U1-PIO4-Pad27)") (class "Default")
      (node (ref "U1") (pin "27") (pinfunction "PIO4_27") (pintype "bidirectional"))
    )
    (net (code "130") (name "unconnected-(U1-PIO5-Pad28)") (class "Default")
      (node (ref "U1") (pin "28") (pinfunction "PIO5_28") (pintype "bidirectional"))
    )
    (net (code "131") (name "unconnected-(U1-PIO6-Pad29)") (class "Default")
      (node (ref "U1") (pin "29") (pinfunction "PIO6_29") (pintype "bidirectional"))
    )
    (net (code "132") (name "unconnected-(U1-PIO7-Pad30)") (class "Default")
      (node (ref "U1") (pin "30") (pinfunction "PIO7_30") (pintype "bidirectional"))
    )
    (net (code "133") (name "unconnected-(U1-PIO9-Pad32)") (class "Default")
      (node (ref "U1") (pin "32") (pinfunction "PIO9_32") (pintype "bidirectional"))
    )
    (net (code "134") (name "unconnected-(U1-PIO10-Pad33)") (class "Default")
      (node (ref "U1") (pin "33") (pinfunction "PIO10_33") (pintype "bidirectional"))
    )
    (net (code "135") (name "unconnected-(U1-RST-Pad11)") (class "Default")
      (node (ref "U1") (pin "11") (pinfunction "RST_11") (pintype "bidirectional"))
    )
    (net (code "136") (name "unconnected-(U1-RTS-Pad4)") (class "Default")
      (node (ref "U1") (pin "4") (pinfunction "RTS_4") (pintype "bidirectional"))
    )
    (net (code "137") (name "unconnected-(U1-VBUSD+-Pad20)") (class "Default")
      (node (ref "U1") (pin "20") (pinfunction "VBUSD+_20") (pintype "bidirectional"))
    )
    (net (code "138") (name "unconnected-(U1-VBUSD--Pad15)") (class "Default")
      (node (ref "U1") (pin "15") (pinfunction "VBUSD-_15") (pintype "bidirectional"))
    )
  )
)
